# axiom_beta_plugin_module_1xPMOD_v0_1_r1_.net
KiCad netlist of a schematic drawn in EAGLE
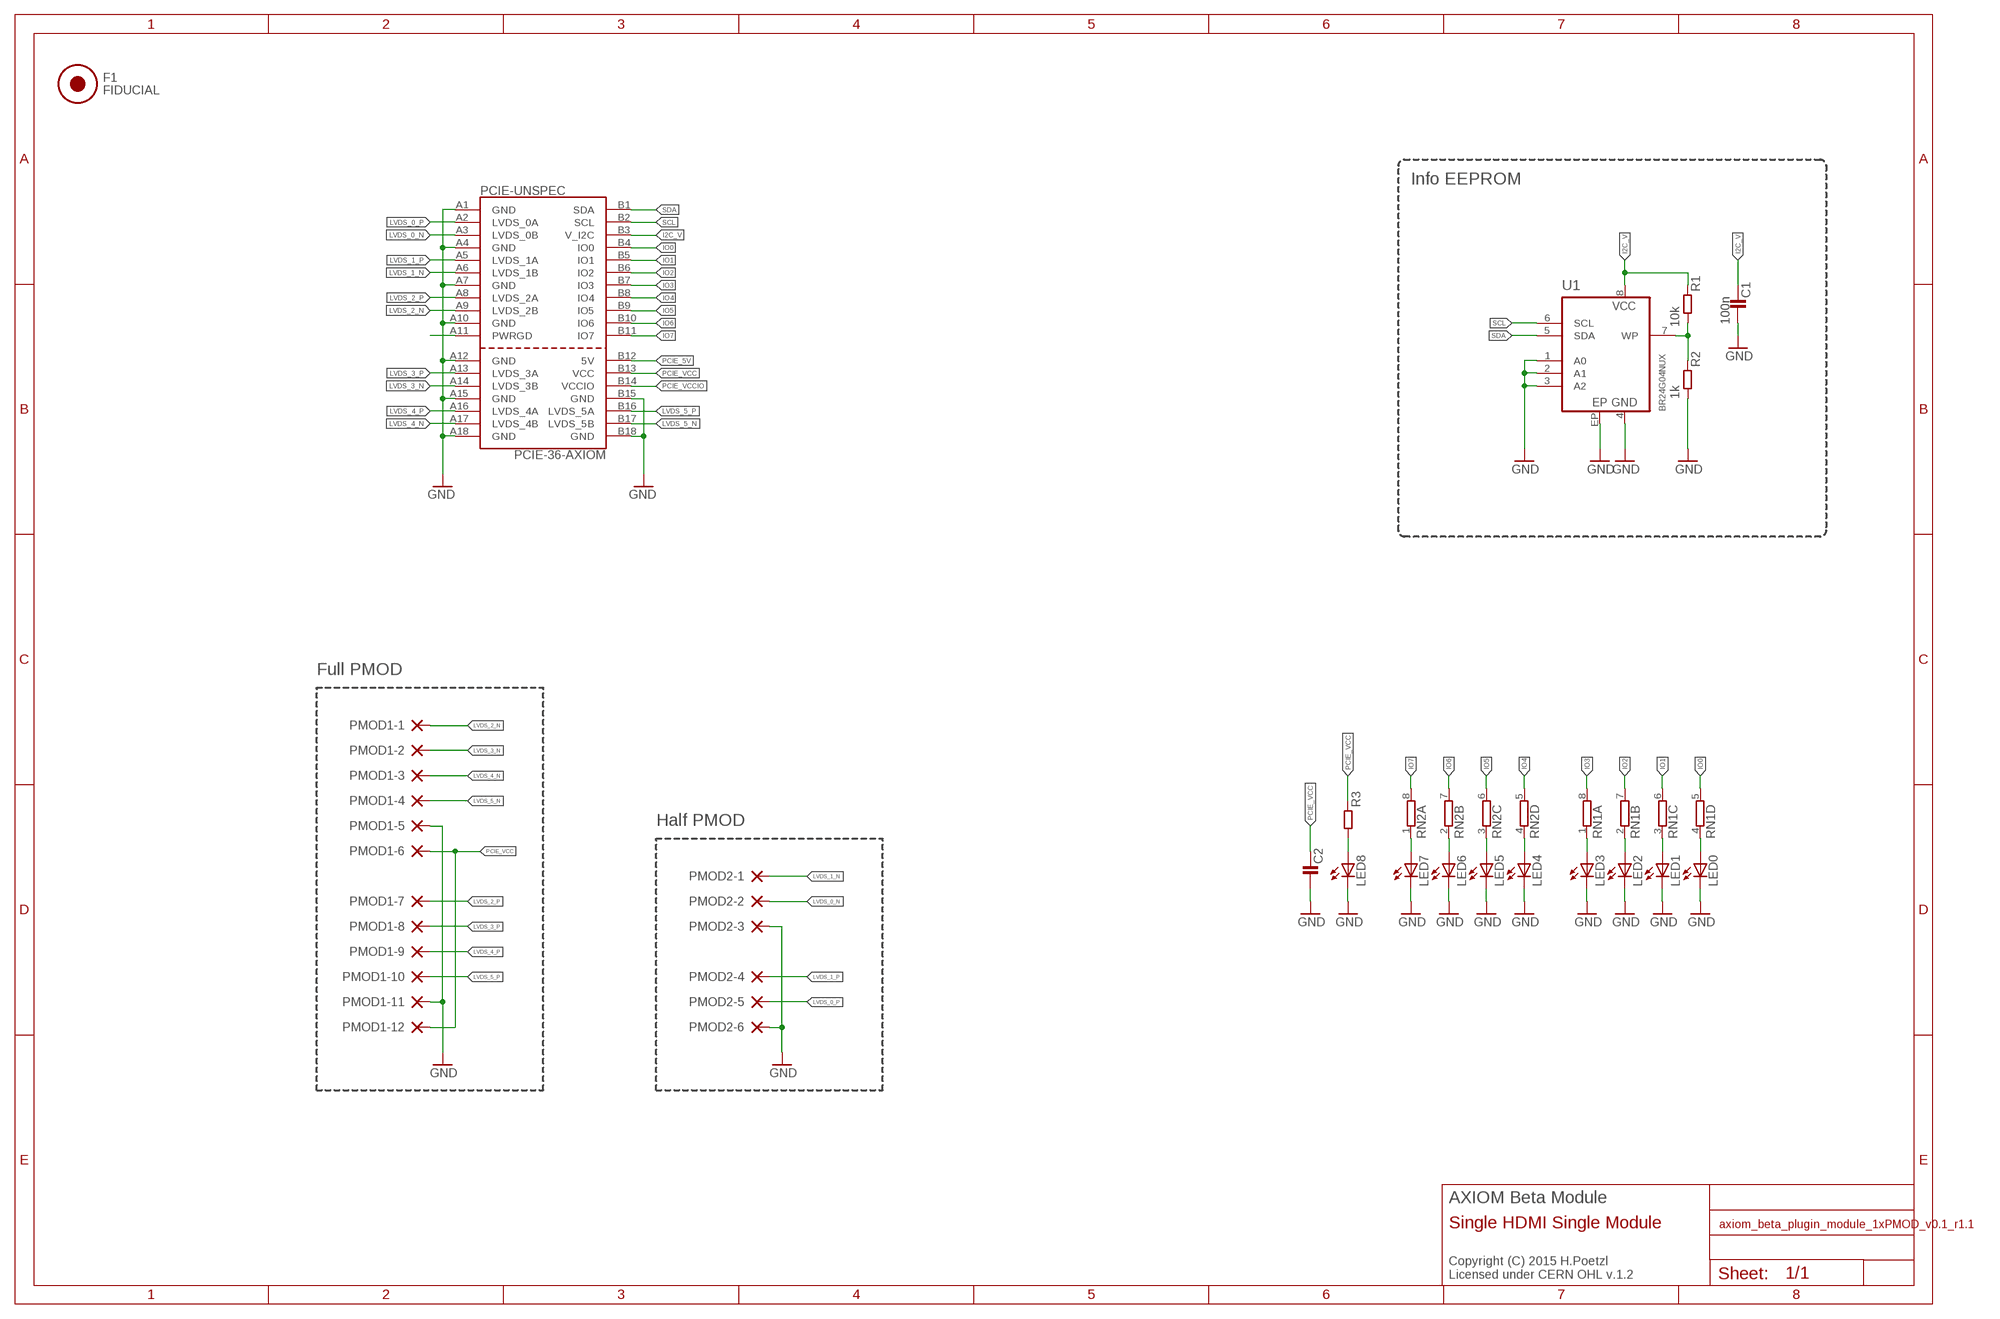
[diagram p0: schematic, sheet 1]

(export (version "E")
  (design (tool "Eeschema 10.0.6"))
  (components
    (comp (ref "C1")
      (value "100n")
      (footprint "eagle-import:0402-B")
      (libsource (lib "eagle-import") (part "C0402-B"))
    )
    (comp (ref "C2")
      (value "C1206-A")
      (footprint "eagle-import:1206-A")
      (libsource (lib "eagle-import") (part "C1206-A"))
    )
    (comp (ref "F1")
      (value "FIDUCIAL")
      (footprint "eagle-import:FID_ARROW")
      (libsource (lib "eagle-import") (part "FIDUCIAL"))
    )
    (comp (ref "LED0")
      (value "LEDCHIPLED_0603")
      (footprint "eagle-import:CHIPLED_0603")
      (libsource (lib "eagle-import") (part "LEDCHIPLED_0603"))
    )
    (comp (ref "LED1")
      (value "LEDCHIPLED_0603")
      (footprint "eagle-import:CHIPLED_0603")
      (libsource (lib "eagle-import") (part "LEDCHIPLED_0603"))
    )
    (comp (ref "LED2")
      (value "LEDCHIPLED_0603")
      (footprint "eagle-import:CHIPLED_0603")
      (libsource (lib "eagle-import") (part "LEDCHIPLED_0603"))
    )
    (comp (ref "LED3")
      (value "LEDCHIPLED_0603")
      (footprint "eagle-import:CHIPLED_0603")
      (libsource (lib "eagle-import") (part "LEDCHIPLED_0603"))
    )
    (comp (ref "LED4")
      (value "LEDCHIPLED_0603")
      (footprint "eagle-import:CHIPLED_0603")
      (libsource (lib "eagle-import") (part "LEDCHIPLED_0603"))
    )
    (comp (ref "LED5")
      (value "LEDCHIPLED_0603")
      (footprint "eagle-import:CHIPLED_0603")
      (libsource (lib "eagle-import") (part "LEDCHIPLED_0603"))
    )
    (comp (ref "LED6")
      (value "LEDCHIPLED_0603")
      (footprint "eagle-import:CHIPLED_0603")
      (libsource (lib "eagle-import") (part "LEDCHIPLED_0603"))
    )
    (comp (ref "LED7")
      (value "LEDCHIPLED_0603")
      (footprint "eagle-import:CHIPLED_0603")
      (libsource (lib "eagle-import") (part "LEDCHIPLED_0603"))
    )
    (comp (ref "LED8")
      (value "LEDCHIPLED_0603")
      (footprint "eagle-import:CHIPLED_0603")
      (libsource (lib "eagle-import") (part "LEDCHIPLED_0603"))
    )
    (comp (ref "PCIE-UNSPEC")
      (value "PCIE-36-AXIOM")
      (footprint "eagle-import:PCIE-36-AXIOM")
      (libsource (lib "eagle-import") (part "PCIE-36-AXIOM"))
    )
    (comp (ref "PMOD1-1")
      (value "SMD-PAD1.6X3.8MM-U")
      (footprint "eagle-import:1.6X3.8U-MM")
      (libsource (lib "eagle-import") (part "SMD-PAD1.6X3.8MM-U"))
    )
    (comp (ref "PMOD1-2")
      (value "SMD-PAD1.6X3.8MM-U")
      (footprint "eagle-import:1.6X3.8U-MM")
      (libsource (lib "eagle-import") (part "SMD-PAD1.6X3.8MM-U"))
    )
    (comp (ref "PMOD1-3")
      (value "SMD-PAD1.6X3.8MM-U")
      (footprint "eagle-import:1.6X3.8U-MM")
      (libsource (lib "eagle-import") (part "SMD-PAD1.6X3.8MM-U"))
    )
    (comp (ref "PMOD1-4")
      (value "SMD-PAD1.6X3.8MM-U")
      (footprint "eagle-import:1.6X3.8U-MM")
      (libsource (lib "eagle-import") (part "SMD-PAD1.6X3.8MM-U"))
    )
    (comp (ref "PMOD1-5")
      (value "SMD-PAD1.6X3.8MM-U")
      (footprint "eagle-import:1.6X3.8U-MM")
      (libsource (lib "eagle-import") (part "SMD-PAD1.6X3.8MM-U"))
    )
    (comp (ref "PMOD1-6")
      (value "SMD-PAD1.6X3.8MM-U")
      (footprint "eagle-import:1.6X3.8U-MM")
      (libsource (lib "eagle-import") (part "SMD-PAD1.6X3.8MM-U"))
    )
    (comp (ref "PMOD1-7")
      (value "SMD-PAD1.6X3.8MM-U")
      (footprint "eagle-import:1.6X3.8U-MM")
      (libsource (lib "eagle-import") (part "SMD-PAD1.6X3.8MM-U"))
    )
    (comp (ref "PMOD1-8")
      (value "SMD-PAD1.6X3.8MM-U")
      (footprint "eagle-import:1.6X3.8U-MM")
      (libsource (lib "eagle-import") (part "SMD-PAD1.6X3.8MM-U"))
    )
    (comp (ref "PMOD1-9")
      (value "SMD-PAD1.6X3.8MM-U")
      (footprint "eagle-import:1.6X3.8U-MM")
      (libsource (lib "eagle-import") (part "SMD-PAD1.6X3.8MM-U"))
    )
    (comp (ref "PMOD1-10")
      (value "SMD-PAD1.6X3.8MM-U")
      (footprint "eagle-import:1.6X3.8U-MM")
      (libsource (lib "eagle-import") (part "SMD-PAD1.6X3.8MM-U"))
    )
    (comp (ref "PMOD1-11")
      (value "SMD-PAD1.6X3.8MM-U")
      (footprint "eagle-import:1.6X3.8U-MM")
      (libsource (lib "eagle-import") (part "SMD-PAD1.6X3.8MM-U"))
    )
    (comp (ref "PMOD1-12")
      (value "SMD-PAD1.6X3.8MM-U")
      (footprint "eagle-import:1.6X3.8U-MM")
      (libsource (lib "eagle-import") (part "SMD-PAD1.6X3.8MM-U"))
    )
    (comp (ref "PMOD2-1")
      (value "SMD-PAD1.6X3.8MM-U")
      (footprint "eagle-import:1.6X3.8U-MM")
      (libsource (lib "eagle-import") (part "SMD-PAD1.6X3.8MM-U"))
    )
    (comp (ref "PMOD2-2")
      (value "SMD-PAD1.6X3.8MM-U")
      (footprint "eagle-import:1.6X3.8U-MM")
      (libsource (lib "eagle-import") (part "SMD-PAD1.6X3.8MM-U"))
    )
    (comp (ref "PMOD2-3")
      (value "SMD-PAD1.6X3.8MM-U")
      (footprint "eagle-import:1.6X3.8U-MM")
      (libsource (lib "eagle-import") (part "SMD-PAD1.6X3.8MM-U"))
    )
    (comp (ref "PMOD2-4")
      (value "SMD-PAD1.6X3.8MM-U")
      (footprint "eagle-import:1.6X3.8U-MM")
      (libsource (lib "eagle-import") (part "SMD-PAD1.6X3.8MM-U"))
    )
    (comp (ref "PMOD2-5")
      (value "SMD-PAD1.6X3.8MM-U")
      (footprint "eagle-import:1.6X3.8U-MM")
      (libsource (lib "eagle-import") (part "SMD-PAD1.6X3.8MM-U"))
    )
    (comp (ref "PMOD2-6")
      (value "SMD-PAD1.6X3.8MM-U")
      (footprint "eagle-import:1.6X3.8U-MM")
      (libsource (lib "eagle-import") (part "SMD-PAD1.6X3.8MM-U"))
    )
    (comp (ref "R1")
      (value "10k")
      (footprint "eagle-import:0402-B")
      (libsource (lib "eagle-import") (part "R0402-B"))
    )
    (comp (ref "R2")
      (value "1k")
      (footprint "eagle-import:0402-B")
      (libsource (lib "eagle-import") (part "R0402-B"))
    )
    (comp (ref "R3")
      (value "R0402-B")
      (footprint "eagle-import:0402-B")
      (libsource (lib "eagle-import") (part "R0402-B"))
    )
    (comp (ref "RN1")
      (value "4R-NCAY16")
      (footprint "eagle-import:CAY16")
      (libsource (lib "eagle-import") (part "4R-NCAY16"))
    )
    (comp (ref "RN2")
      (value "4R-NCAY16")
      (footprint "eagle-import:CAY16")
      (libsource (lib "eagle-import") (part "4R-NCAY16"))
    )
    (comp (ref "U1")
      (value "BR24G04NUX")
      (footprint "eagle-import:DFN200X300X100-9N")
      (libsource (lib "eagle-import") (part "BR24G04NUX"))
    )
  )
  (nets
    (net (code "1") (name "GND") (class "Default")
      (node (ref "C1") (pin "2") (pinfunction "2_2") (pintype "passive"))
      (node (ref "C2") (pin "2") (pinfunction "2_2") (pintype "passive"))
      (node (ref "LED0") (pin "C") (pinfunction "C_C") (pintype "passive"))
      (node (ref "LED1") (pin "C") (pinfunction "C_C") (pintype "passive"))
      (node (ref "LED2") (pin "C") (pinfunction "C_C") (pintype "passive"))
      (node (ref "LED3") (pin "C") (pinfunction "C_C") (pintype "passive"))
      (node (ref "LED4") (pin "C") (pinfunction "C_C") (pintype "passive"))
      (node (ref "LED5") (pin "C") (pinfunction "C_C") (pintype "passive"))
      (node (ref "LED6") (pin "C") (pinfunction "C_C") (pintype "passive"))
      (node (ref "LED7") (pin "C") (pinfunction "C_C") (pintype "passive"))
      (node (ref "LED8") (pin "C") (pinfunction "C_C") (pintype "passive"))
      (node (ref "PCIE-UNSPEC") (pin "A1") (pinfunction "GND_A1") (pintype "passive"))
      (node (ref "PCIE-UNSPEC") (pin "A10") (pinfunction "GND_A10") (pintype "passive"))
      (node (ref "PCIE-UNSPEC") (pin "A12") (pinfunction "GND_A12") (pintype "passive"))
      (node (ref "PCIE-UNSPEC") (pin "A15") (pinfunction "GND_A15") (pintype "passive"))
      (node (ref "PCIE-UNSPEC") (pin "A18") (pinfunction "GND_A18") (pintype "passive"))
      (node (ref "PCIE-UNSPEC") (pin "A4") (pinfunction "GND_A4") (pintype "passive"))
      (node (ref "PCIE-UNSPEC") (pin "A7") (pinfunction "GND_A7") (pintype "passive"))
      (node (ref "PCIE-UNSPEC") (pin "B15") (pinfunction "GND_B15") (pintype "passive"))
      (node (ref "PCIE-UNSPEC") (pin "B18") (pinfunction "GND_B18") (pintype "passive"))
      (node (ref "PMOD1-11") (pin "1") (pinfunction "P_1") (pintype "passive"))
      (node (ref "PMOD1-5") (pin "1") (pinfunction "P_1") (pintype "passive"))
      (node (ref "PMOD2-3") (pin "1") (pinfunction "P_1") (pintype "passive"))
      (node (ref "PMOD2-6") (pin "1") (pinfunction "P_1") (pintype "passive"))
      (node (ref "R2") (pin "2") (pinfunction "2_2") (pintype "passive"))
      (node (ref "U1") (pin "1") (pinfunction "A0_1") (pintype "input"))
      (node (ref "U1") (pin "2") (pinfunction "A1_2") (pintype "input"))
      (node (ref "U1") (pin "3") (pinfunction "A2_3") (pintype "input"))
      (node (ref "U1") (pin "4") (pinfunction "GND_4") (pintype "passive"))
      (node (ref "U1") (pin "EP") (pinfunction "EP_EP") (pintype "passive"))
    )
    (net (code "2") (name "I2C_V") (class "Default")
      (node (ref "C1") (pin "1") (pinfunction "1_1") (pintype "passive"))
      (node (ref "PCIE-UNSPEC") (pin "B3") (pinfunction "V_I2C_B3") (pintype "passive"))
      (node (ref "R1") (pin "1") (pinfunction "1_1") (pintype "passive"))
      (node (ref "U1") (pin "8") (pinfunction "VCC_8") (pintype "power_in"))
    )
    (net (code "3") (name "IO0") (class "Default")
      (node (ref "PCIE-UNSPEC") (pin "B4") (pinfunction "IO0_B4") (pintype "passive"))
      (node (ref "RN1") (pin "5") (pinfunction "2_5") (pintype "passive"))
    )
    (net (code "4") (name "IO1") (class "Default")
      (node (ref "PCIE-UNSPEC") (pin "B5") (pinfunction "IO1_B5") (pintype "passive"))
      (node (ref "RN1") (pin "6") (pinfunction "2_6") (pintype "passive"))
    )
    (net (code "5") (name "IO2") (class "Default")
      (node (ref "PCIE-UNSPEC") (pin "B6") (pinfunction "IO2_B6") (pintype "passive"))
      (node (ref "RN1") (pin "7") (pinfunction "2_7") (pintype "passive"))
    )
    (net (code "6") (name "IO3") (class "Default")
      (node (ref "PCIE-UNSPEC") (pin "B7") (pinfunction "IO3_B7") (pintype "passive"))
      (node (ref "RN1") (pin "8") (pinfunction "2_8") (pintype "passive"))
    )
    (net (code "7") (name "IO4") (class "Default")
      (node (ref "PCIE-UNSPEC") (pin "B8") (pinfunction "IO4_B8") (pintype "passive"))
      (node (ref "RN2") (pin "5") (pinfunction "2_5") (pintype "passive"))
    )
    (net (code "8") (name "IO5") (class "Default")
      (node (ref "PCIE-UNSPEC") (pin "B9") (pinfunction "IO5_B9") (pintype "passive"))
      (node (ref "RN2") (pin "6") (pinfunction "2_6") (pintype "passive"))
    )
    (net (code "9") (name "IO6") (class "Default")
      (node (ref "PCIE-UNSPEC") (pin "B10") (pinfunction "IO6_B10") (pintype "passive"))
      (node (ref "RN2") (pin "7") (pinfunction "2_7") (pintype "passive"))
    )
    (net (code "10") (name "IO7") (class "Default")
      (node (ref "PCIE-UNSPEC") (pin "B11") (pinfunction "IO7_B11") (pintype "passive"))
      (node (ref "RN2") (pin "8") (pinfunction "2_8") (pintype "passive"))
    )
    (net (code "11") (name "LVDS_0_N") (class "Default")
      (node (ref "PCIE-UNSPEC") (pin "A3") (pinfunction "LVDS_0B_A3") (pintype "passive"))
      (node (ref "PMOD2-2") (pin "1") (pinfunction "P_1") (pintype "passive"))
    )
    (net (code "12") (name "LVDS_0_P") (class "Default")
      (node (ref "PCIE-UNSPEC") (pin "A2") (pinfunction "LVDS_0A_A2") (pintype "passive"))
      (node (ref "PMOD2-5") (pin "1") (pinfunction "P_1") (pintype "passive"))
    )
    (net (code "13") (name "LVDS_1_N") (class "Default")
      (node (ref "PCIE-UNSPEC") (pin "A6") (pinfunction "LVDS_1B_A6") (pintype "passive"))
      (node (ref "PMOD2-1") (pin "1") (pinfunction "P_1") (pintype "passive"))
    )
    (net (code "14") (name "LVDS_1_P") (class "Default")
      (node (ref "PCIE-UNSPEC") (pin "A5") (pinfunction "LVDS_1A_A5") (pintype "passive"))
      (node (ref "PMOD2-4") (pin "1") (pinfunction "P_1") (pintype "passive"))
    )
    (net (code "15") (name "LVDS_2_N") (class "Default")
      (node (ref "PCIE-UNSPEC") (pin "A9") (pinfunction "LVDS_2B_A9") (pintype "passive"))
      (node (ref "PMOD1-1") (pin "1") (pinfunction "P_1") (pintype "passive"))
    )
    (net (code "16") (name "LVDS_2_P") (class "Default")
      (node (ref "PCIE-UNSPEC") (pin "A8") (pinfunction "LVDS_2A_A8") (pintype "passive"))
      (node (ref "PMOD1-7") (pin "1") (pinfunction "P_1") (pintype "passive"))
    )
    (net (code "17") (name "LVDS_3_N") (class "Default")
      (node (ref "PCIE-UNSPEC") (pin "A14") (pinfunction "LVDS_3B_A14") (pintype "passive"))
      (node (ref "PMOD1-2") (pin "1") (pinfunction "P_1") (pintype "passive"))
    )
    (net (code "18") (name "LVDS_3_P") (class "Default")
      (node (ref "PCIE-UNSPEC") (pin "A13") (pinfunction "LVDS_3A_A13") (pintype "passive"))
      (node (ref "PMOD1-8") (pin "1") (pinfunction "P_1") (pintype "passive"))
    )
    (net (code "19") (name "LVDS_4_N") (class "Default")
      (node (ref "PCIE-UNSPEC") (pin "A17") (pinfunction "LVDS_4B_A17") (pintype "passive"))
      (node (ref "PMOD1-3") (pin "1") (pinfunction "P_1") (pintype "passive"))
    )
    (net (code "20") (name "LVDS_4_P") (class "Default")
      (node (ref "PCIE-UNSPEC") (pin "A16") (pinfunction "LVDS_4A_A16") (pintype "passive"))
      (node (ref "PMOD1-9") (pin "1") (pinfunction "P_1") (pintype "passive"))
    )
    (net (code "21") (name "LVDS_5_N") (class "Default")
      (node (ref "PCIE-UNSPEC") (pin "B17") (pinfunction "LVDS_5B_B17") (pintype "passive"))
      (node (ref "PMOD1-4") (pin "1") (pinfunction "P_1") (pintype "passive"))
    )
    (net (code "22") (name "LVDS_5_P") (class "Default")
      (node (ref "PCIE-UNSPEC") (pin "B16") (pinfunction "LVDS_5A_B16") (pintype "passive"))
      (node (ref "PMOD1-10") (pin "1") (pinfunction "P_1") (pintype "passive"))
    )
    (net (code "23") (name "Net-(LED3-PadA)") (class "Default")
      (node (ref "LED3") (pin "A") (pinfunction "A_A") (pintype "passive"))
      (node (ref "RN1") (pin "1") (pinfunction "1_1") (pintype "passive"))
    )
    (net (code "24") (name "Net-(LED7-PadA)") (class "Default")
      (node (ref "LED7") (pin "A") (pinfunction "A_A") (pintype "passive"))
      (node (ref "RN2") (pin "1") (pinfunction "1_1") (pintype "passive"))
    )
    (net (code "25") (name "Net-(LED8-PadA)") (class "Default")
      (node (ref "LED8") (pin "A") (pinfunction "A_A") (pintype "passive"))
      (node (ref "R3") (pin "2") (pinfunction "2_2") (pintype "passive"))
    )
    (net (code "26") (name "Net-(RN1B-1)") (class "Default")
      (node (ref "LED2") (pin "A") (pinfunction "A_A") (pintype "passive"))
      (node (ref "RN1") (pin "2") (pinfunction "1_2") (pintype "passive"))
    )
    (net (code "27") (name "Net-(RN1C-1)") (class "Default")
      (node (ref "LED1") (pin "A") (pinfunction "A_A") (pintype "passive"))
      (node (ref "RN1") (pin "3") (pinfunction "1_3") (pintype "passive"))
    )
    (net (code "28") (name "Net-(RN1D-1)") (class "Default")
      (node (ref "LED0") (pin "A") (pinfunction "A_A") (pintype "passive"))
      (node (ref "RN1") (pin "4") (pinfunction "1_4") (pintype "passive"))
    )
    (net (code "29") (name "Net-(RN2B-1)") (class "Default")
      (node (ref "LED6") (pin "A") (pinfunction "A_A") (pintype "passive"))
      (node (ref "RN2") (pin "2") (pinfunction "1_2") (pintype "passive"))
    )
    (net (code "30") (name "Net-(RN2C-1)") (class "Default")
      (node (ref "LED5") (pin "A") (pinfunction "A_A") (pintype "passive"))
      (node (ref "RN2") (pin "3") (pinfunction "1_3") (pintype "passive"))
    )
    (net (code "31") (name "Net-(RN2D-1)") (class "Default")
      (node (ref "LED4") (pin "A") (pinfunction "A_A") (pintype "passive"))
      (node (ref "RN2") (pin "4") (pinfunction "1_4") (pintype "passive"))
    )
    (net (code "32") (name "Net-(U1-WP)") (class "Default")
      (node (ref "R1") (pin "2") (pinfunction "2_2") (pintype "passive"))
      (node (ref "R2") (pin "1") (pinfunction "1_1") (pintype "passive"))
      (node (ref "U1") (pin "7") (pinfunction "WP_7") (pintype "input"))
    )
    (net (code "33") (name "PCIE_5V") (class "Default")
      (node (ref "PCIE-UNSPEC") (pin "B12") (pinfunction "5V_B12") (pintype "passive"))
    )
    (net (code "34") (name "PCIE_VCC") (class "Default")
      (node (ref "C2") (pin "1") (pinfunction "1_1") (pintype "passive"))
      (node (ref "PCIE-UNSPEC") (pin "B13") (pinfunction "VCC_B13") (pintype "passive"))
      (node (ref "PMOD1-12") (pin "1") (pinfunction "P_1") (pintype "passive"))
      (node (ref "PMOD1-6") (pin "1") (pinfunction "P_1") (pintype "passive"))
      (node (ref "R3") (pin "1") (pinfunction "1_1") (pintype "passive"))
    )
    (net (code "35") (name "PCIE_VCCIO") (class "Default")
      (node (ref "PCIE-UNSPEC") (pin "B14") (pinfunction "VCCIO_B14") (pintype "passive"))
    )
    (net (code "36") (name "SCL") (class "Default")
      (node (ref "PCIE-UNSPEC") (pin "B2") (pinfunction "SCL_B2") (pintype "passive"))
      (node (ref "U1") (pin "6") (pinfunction "SCL_6") (pintype "input"))
    )
    (net (code "37") (name "SDA") (class "Default")
      (node (ref "PCIE-UNSPEC") (pin "B1") (pinfunction "SDA_B1") (pintype "passive"))
      (node (ref "U1") (pin "5") (pinfunction "SDA_5") (pintype "bidirectional"))
    )
    (net (code "38") (name "unconnected-(PCIE-UNSPEC-PWRGD-PadA11)") (class "Default")
      (node (ref "PCIE-UNSPEC") (pin "A11") (pinfunction "PWRGD_A11") (pintype "passive"))
    )
  )
)
